# OneButton.net
KiCad netlist of a schematic drawn in EAGLE
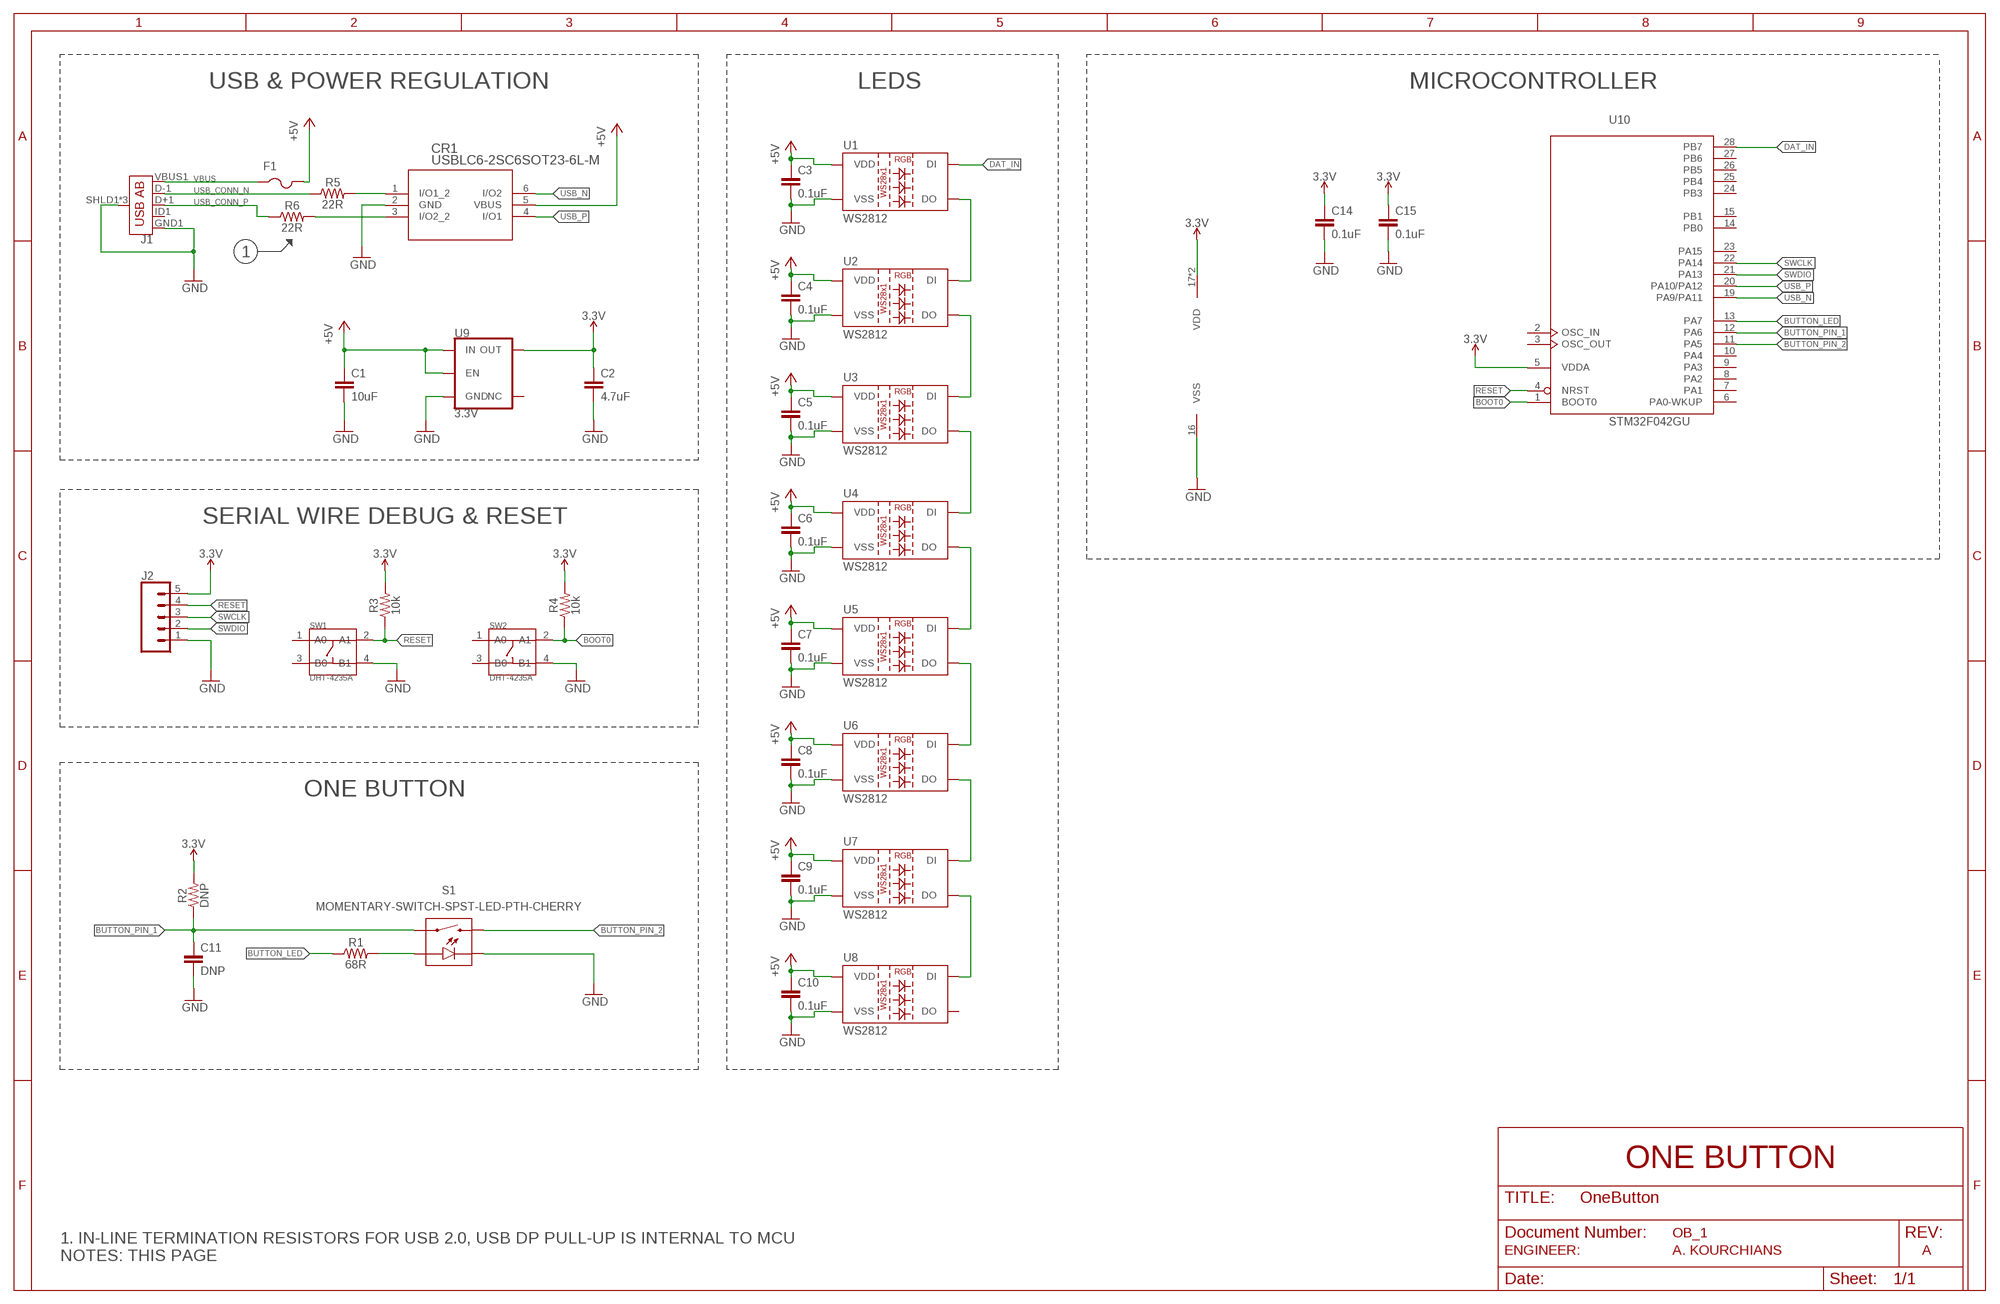
[diagram p0: schematic, sheet 1]

(export (version "E")
  (design (tool "Eeschema 10.0.6"))
  (components
    (comp (ref "C1")
      (value "10uF")
      (footprint "eagle-import:CAP-1206")
      (libsource (lib "eagle-import") (part "10UFCAP-1206"))
    )
    (comp (ref "C2")
      (value "4.7uF")
      (footprint "eagle-import:CAP-1206")
      (libsource (lib "eagle-import") (part "4.7UFCAP-1206"))
    )
    (comp (ref "C3")
      (value "0.1uF")
      (footprint "eagle-import:CAP-0603")
      (libsource (lib "eagle-import") (part "0.1UFCAP-0603"))
    )
    (comp (ref "C4")
      (value "0.1uF")
      (footprint "eagle-import:CAP-0603")
      (libsource (lib "eagle-import") (part "0.1UFCAP-0603"))
    )
    (comp (ref "C5")
      (value "0.1uF")
      (footprint "eagle-import:CAP-0603")
      (libsource (lib "eagle-import") (part "0.1UFCAP-0603"))
    )
    (comp (ref "C6")
      (value "0.1uF")
      (footprint "eagle-import:CAP-0603")
      (libsource (lib "eagle-import") (part "0.1UFCAP-0603"))
    )
    (comp (ref "C7")
      (value "0.1uF")
      (footprint "eagle-import:CAP-0603")
      (libsource (lib "eagle-import") (part "0.1UFCAP-0603"))
    )
    (comp (ref "C8")
      (value "0.1uF")
      (footprint "eagle-import:CAP-0603")
      (libsource (lib "eagle-import") (part "0.1UFCAP-0603"))
    )
    (comp (ref "C9")
      (value "0.1uF")
      (footprint "eagle-import:CAP-0603")
      (libsource (lib "eagle-import") (part "0.1UFCAP-0603"))
    )
    (comp (ref "C10")
      (value "0.1uF")
      (footprint "eagle-import:CAP-0603")
      (libsource (lib "eagle-import") (part "0.1UFCAP-0603"))
    )
    (comp (ref "C11")
      (value "DNP")
      (footprint "eagle-import:CAP-0603")
      (libsource (lib "eagle-import") (part "CAPACITORCAP-0603"))
    )
    (comp (ref "C14")
      (value "0.1uF")
      (footprint "eagle-import:CAP-0603")
      (libsource (lib "eagle-import") (part "0.1UFCAP-0603"))
    )
    (comp (ref "C15")
      (value "0.1uF")
      (footprint "eagle-import:CAP-0603")
      (libsource (lib "eagle-import") (part "0.1UFCAP-0603"))
    )
    (comp (ref "CR1")
      (value "USBLC6-2SC6SOT23-6L-M")
      (footprint "eagle-import:SOT23-6L-M")
      (fields (field (name "MANUFACTURER_PART_NUMBER") "USBLC62SC6"))
      (libsource (lib "eagle-import") (part "USBLC6-2SC6SOT23-6L-M"))
    )
    (comp (ref "F1")
      (value "PTCFUSE-1206")
      (footprint "eagle-import:R1206")
      (libsource (lib "eagle-import") (part "PTCFUSE-1206"))
    )
    (comp (ref "J1")
      (value "USB_AB_SMT")
      (footprint "eagle-import:USB-AB-MICRO-SMD")
      (libsource (lib "eagle-import") (part "USB_AB_SMT"))
    )
    (comp (ref "J2")
      (value "CONN_05")
      (footprint "eagle-import:1X05")
      (libsource (lib "eagle-import") (part "CONN_05"))
    )
    (comp (ref "R1")
      (value "68R")
      (footprint "eagle-import:RESC0603_N")
      (libsource (lib "eagle-import") (part "RESISTORRES-0603"))
    )
    (comp (ref "R2")
      (value "DNP")
      (footprint "eagle-import:RESC0603_N")
      (libsource (lib "eagle-import") (part "RESISTORRES-0603"))
    )
    (comp (ref "R3")
      (value "10k")
      (footprint "eagle-import:RESC0603_N")
      (libsource (lib "eagle-import") (part "RESISTORRES-0603"))
    )
    (comp (ref "R4")
      (value "10k")
      (footprint "eagle-import:RESC0603_N")
      (libsource (lib "eagle-import") (part "RESISTORRES-0603"))
    )
    (comp (ref "R5")
      (value "22R")
      (footprint "eagle-import:RESC0603_N")
      (libsource (lib "eagle-import") (part "RESISTORRES-0603"))
    )
    (comp (ref "R6")
      (value "22R")
      (footprint "eagle-import:RESC0603_N")
      (libsource (lib "eagle-import") (part "RESISTORRES-0603"))
    )
    (comp (ref "S1")
      (value "MOMENTARY-SWITCH-SPST-LED-PTH-CHERRY")
      (footprint "eagle-import:CHERRY-MX-LED")
      (fields (field (name "SPICEPREFIX") "S"))
      (libsource (lib "eagle-import") (part "MOMENTARY-SWITCH-SPST-LED-PTH-CHERRY"))
    )
    (comp (ref "SW1")
      (value "DHT-4235A")
      (footprint "eagle-import:SW4-SMD-4.2X3.2X2.5MM")
      (libsource (lib "eagle-import") (part "SMD-BUTTON-TOP-DHT-4235A(4P-4.2X3.2MM)"))
    )
    (comp (ref "SW2")
      (value "DHT-4235A")
      (footprint "eagle-import:SW4-SMD-4.2X3.2X2.5MM")
      (libsource (lib "eagle-import") (part "SMD-BUTTON-TOP-DHT-4235A(4P-4.2X3.2MM)"))
    )
    (comp (ref "U1")
      (value "WS2812")
      (footprint "eagle-import:LED-TRICOLOR-5050-IC")
      (libsource (lib "eagle-import") (part "WS2812{dblquote}"))
    )
    (comp (ref "U2")
      (value "WS2812")
      (footprint "eagle-import:LED-TRICOLOR-5050-IC")
      (libsource (lib "eagle-import") (part "WS2812{dblquote}"))
    )
    (comp (ref "U3")
      (value "WS2812")
      (footprint "eagle-import:LED-TRICOLOR-5050-IC")
      (libsource (lib "eagle-import") (part "WS2812{dblquote}"))
    )
    (comp (ref "U4")
      (value "WS2812")
      (footprint "eagle-import:LED-TRICOLOR-5050-IC")
      (libsource (lib "eagle-import") (part "WS2812{dblquote}"))
    )
    (comp (ref "U5")
      (value "WS2812")
      (footprint "eagle-import:LED-TRICOLOR-5050-IC")
      (libsource (lib "eagle-import") (part "WS2812{dblquote}"))
    )
    (comp (ref "U6")
      (value "WS2812")
      (footprint "eagle-import:LED-TRICOLOR-5050-IC")
      (libsource (lib "eagle-import") (part "WS2812{dblquote}"))
    )
    (comp (ref "U7")
      (value "WS2812")
      (footprint "eagle-import:LED-TRICOLOR-5050-IC")
      (libsource (lib "eagle-import") (part "WS2812{dblquote}"))
    )
    (comp (ref "U8")
      (value "WS2812")
      (footprint "eagle-import:LED-TRICOLOR-5050-IC")
      (libsource (lib "eagle-import") (part "WS2812{dblquote}"))
    )
    (comp (ref "U9")
      (value "3.3V")
      (footprint "eagle-import:SOT23-5")
      (libsource (lib "eagle-import") (part "V_REG_AP2112K-3.3V"))
    )
    (comp (ref "U10")
      (value "STM32F042GU")
      (footprint "eagle-import:UFQFPN28")
      (libsource (lib "eagle-import") (part "STM32F042GU"))
    )
  )
  (nets
    (net (code "1") (name "+5V") (class "Default")
      (node (ref "C1") (pin "1") (pinfunction "1_1") (pintype "passive"))
      (node (ref "C10") (pin "1") (pinfunction "1_1") (pintype "passive"))
      (node (ref "C3") (pin "1") (pinfunction "1_1") (pintype "passive"))
      (node (ref "C4") (pin "1") (pinfunction "1_1") (pintype "passive"))
      (node (ref "C5") (pin "1") (pinfunction "1_1") (pintype "passive"))
      (node (ref "C6") (pin "1") (pinfunction "1_1") (pintype "passive"))
      (node (ref "C7") (pin "1") (pinfunction "1_1") (pintype "passive"))
      (node (ref "C8") (pin "1") (pinfunction "1_1") (pintype "passive"))
      (node (ref "C9") (pin "1") (pinfunction "1_1") (pintype "passive"))
      (node (ref "CR1") (pin "5") (pinfunction "VBUS_5") (pintype "power_in"))
      (node (ref "F1") (pin "2") (pinfunction "2_2") (pintype "passive"))
      (node (ref "U1") (pin "3") (pinfunction "VDD_3") (pintype "bidirectional"))
      (node (ref "U1") (pin "5") (pinfunction "VDD_5") (pintype "bidirectional"))
      (node (ref "U2") (pin "3") (pinfunction "VDD_3") (pintype "bidirectional"))
      (node (ref "U2") (pin "5") (pinfunction "VDD_5") (pintype "bidirectional"))
      (node (ref "U3") (pin "3") (pinfunction "VDD_3") (pintype "bidirectional"))
      (node (ref "U3") (pin "5") (pinfunction "VDD_5") (pintype "bidirectional"))
      (node (ref "U4") (pin "3") (pinfunction "VDD_3") (pintype "bidirectional"))
      (node (ref "U4") (pin "5") (pinfunction "VDD_5") (pintype "bidirectional"))
      (node (ref "U5") (pin "3") (pinfunction "VDD_3") (pintype "bidirectional"))
      (node (ref "U5") (pin "5") (pinfunction "VDD_5") (pintype "bidirectional"))
      (node (ref "U6") (pin "3") (pinfunction "VDD_3") (pintype "bidirectional"))
      (node (ref "U6") (pin "5") (pinfunction "VDD_5") (pintype "bidirectional"))
      (node (ref "U7") (pin "3") (pinfunction "VDD_3") (pintype "bidirectional"))
      (node (ref "U7") (pin "5") (pinfunction "VDD_5") (pintype "bidirectional"))
      (node (ref "U8") (pin "3") (pinfunction "VDD_3") (pintype "bidirectional"))
      (node (ref "U8") (pin "5") (pinfunction "VDD_5") (pintype "bidirectional"))
      (node (ref "U9") (pin "1") (pinfunction "IN_1") (pintype "input"))
      (node (ref "U9") (pin "3") (pinfunction "EN_3") (pintype "input"))
    )
    (net (code "2") (name "/USB_CONN_N") (class "Default")
      (node (ref "J1") (pin "D-1") (pinfunction "D-_D-1") (pintype "bidirectional"))
      (node (ref "R5") (pin "1") (pinfunction "1_1") (pintype "passive"))
    )
    (net (code "3") (name "/USB_CONN_P") (class "Default")
      (node (ref "J1") (pin "D+1") (pinfunction "D+_D+1") (pintype "bidirectional"))
      (node (ref "R6") (pin "1") (pinfunction "1_1") (pintype "passive"))
    )
    (net (code "4") (name "/VBUS") (class "Default")
      (node (ref "F1") (pin "1") (pinfunction "1_1") (pintype "passive"))
      (node (ref "J1") (pin "VBUS1") (pinfunction "VBUS_VBUS1") (pintype "power_in"))
    )
    (net (code "5") (name "3.3V") (class "Default")
      (node (ref "C14") (pin "1") (pinfunction "1_1") (pintype "passive"))
      (node (ref "C15") (pin "1") (pinfunction "1_1") (pintype "passive"))
      (node (ref "C2") (pin "1") (pinfunction "1_1") (pintype "passive"))
      (node (ref "J2") (pin "5") (pinfunction "5_5") (pintype "passive"))
      (node (ref "R2") (pin "2") (pinfunction "2_2") (pintype "passive"))
      (node (ref "R3") (pin "2") (pinfunction "2_2") (pintype "passive"))
      (node (ref "R4") (pin "2") (pinfunction "2_2") (pintype "passive"))
      (node (ref "U10") (pin "17") (pinfunction "VDD_17") (pintype "power_in"))
      (node (ref "U10") (pin "18") (pinfunction "VDD_18") (pintype "power_in"))
      (node (ref "U10") (pin "5") (pinfunction "VDDA_5") (pintype "power_in"))
      (node (ref "U9") (pin "5") (pinfunction "OUT_5") (pintype "passive"))
    )
    (net (code "6") (name "BOOT0") (class "Default")
      (node (ref "R4") (pin "1") (pinfunction "1_1") (pintype "passive"))
      (node (ref "SW2") (pin "2") (pinfunction "A1_2") (pintype "bidirectional"))
      (node (ref "U10") (pin "1") (pinfunction "BOOT0_1") (pintype "input"))
    )
    (net (code "7") (name "BUTTON_LED") (class "Default")
      (node (ref "R1") (pin "1") (pinfunction "1_1") (pintype "passive"))
      (node (ref "U10") (pin "13") (pinfunction "PA7_13") (pintype "bidirectional"))
    )
    (net (code "8") (name "BUTTON_PIN_1") (class "Default")
      (node (ref "C11") (pin "1") (pinfunction "1_1") (pintype "passive"))
      (node (ref "R2") (pin "1") (pinfunction "1_1") (pintype "passive"))
      (node (ref "S1") (pin "S1") (pinfunction "1_S1") (pintype "passive"))
      (node (ref "U10") (pin "12") (pinfunction "PA6_12") (pintype "bidirectional"))
    )
    (net (code "9") (name "BUTTON_PIN_2") (class "Default")
      (node (ref "S1") (pin "S2") (pinfunction "2_S2") (pintype "passive"))
      (node (ref "U10") (pin "11") (pinfunction "PA5_11") (pintype "bidirectional"))
    )
    (net (code "10") (name "DAT_IN") (class "Default")
      (node (ref "U1") (pin "2") (pinfunction "DI_2") (pintype "bidirectional"))
      (node (ref "U10") (pin "28") (pinfunction "PB7_28") (pintype "bidirectional"))
    )
    (net (code "11") (name "GND") (class "Default")
      (node (ref "C1") (pin "2") (pinfunction "2_2") (pintype "passive"))
      (node (ref "C10") (pin "2") (pinfunction "2_2") (pintype "passive"))
      (node (ref "C11") (pin "2") (pinfunction "2_2") (pintype "passive"))
      (node (ref "C14") (pin "2") (pinfunction "2_2") (pintype "passive"))
      (node (ref "C15") (pin "2") (pinfunction "2_2") (pintype "passive"))
      (node (ref "C2") (pin "2") (pinfunction "2_2") (pintype "passive"))
      (node (ref "C3") (pin "2") (pinfunction "2_2") (pintype "passive"))
      (node (ref "C4") (pin "2") (pinfunction "2_2") (pintype "passive"))
      (node (ref "C5") (pin "2") (pinfunction "2_2") (pintype "passive"))
      (node (ref "C6") (pin "2") (pinfunction "2_2") (pintype "passive"))
      (node (ref "C7") (pin "2") (pinfunction "2_2") (pintype "passive"))
      (node (ref "C8") (pin "2") (pinfunction "2_2") (pintype "passive"))
      (node (ref "C9") (pin "2") (pinfunction "2_2") (pintype "passive"))
      (node (ref "CR1") (pin "2") (pinfunction "GND_2") (pintype "power_in"))
      (node (ref "J1") (pin "GND1") (pinfunction "GND_GND1") (pintype "power_in"))
      (node (ref "J1") (pin "SHLD1") (pinfunction "SHIELD_SHLD1") (pintype "bidirectional"))
      (node (ref "J1") (pin "SHLD2") (pinfunction "SHIELD_SHLD2") (pintype "bidirectional"))
      (node (ref "J1") (pin "SHLD3") (pinfunction "SHIELD_SHLD3") (pintype "bidirectional"))
      (node (ref "J2") (pin "1") (pinfunction "1_1") (pintype "passive"))
      (node (ref "S1") (pin "K") (pinfunction "C_K") (pintype "passive"))
      (node (ref "S1") (pin "K1") (pinfunction "C_K1") (pintype "passive"))
      (node (ref "SW1") (pin "4") (pinfunction "B1_4") (pintype "bidirectional"))
      (node (ref "SW2") (pin "4") (pinfunction "B1_4") (pintype "bidirectional"))
      (node (ref "U1") (pin "6") (pinfunction "VSS_6") (pintype "bidirectional"))
      (node (ref "U10") (pin "16") (pinfunction "VSS_16") (pintype "power_in"))
      (node (ref "U2") (pin "6") (pinfunction "VSS_6") (pintype "bidirectional"))
      (node (ref "U3") (pin "6") (pinfunction "VSS_6") (pintype "bidirectional"))
      (node (ref "U4") (pin "6") (pinfunction "VSS_6") (pintype "bidirectional"))
      (node (ref "U5") (pin "6") (pinfunction "VSS_6") (pintype "bidirectional"))
      (node (ref "U6") (pin "6") (pinfunction "VSS_6") (pintype "bidirectional"))
      (node (ref "U7") (pin "6") (pinfunction "VSS_6") (pintype "bidirectional"))
      (node (ref "U8") (pin "6") (pinfunction "VSS_6") (pintype "bidirectional"))
      (node (ref "U9") (pin "2") (pinfunction "GND_2") (pintype "input"))
    )
    (net (code "12") (name "Net-(CR1-I{slash}O1_2)") (class "Default")
      (node (ref "CR1") (pin "1") (pinfunction "I/O1_2_1") (pintype "bidirectional"))
      (node (ref "R5") (pin "2") (pinfunction "2_2") (pintype "passive"))
    )
    (net (code "13") (name "Net-(CR1-I{slash}O2_2)") (class "Default")
      (node (ref "CR1") (pin "3") (pinfunction "I/O2_2_3") (pintype "bidirectional"))
      (node (ref "R6") (pin "2") (pinfunction "2_2") (pintype "passive"))
    )
    (net (code "14") (name "Net-(R1-Pad2)") (class "Default")
      (node (ref "R1") (pin "2") (pinfunction "2_2") (pintype "passive"))
      (node (ref "S1") (pin "A") (pinfunction "A_A") (pintype "passive"))
      (node (ref "S1") (pin "A1") (pinfunction "A_A1") (pintype "passive"))
    )
    (net (code "15") (name "Net-(U1-DO)") (class "Default")
      (node (ref "U1") (pin "1") (pinfunction "DO_1") (pintype "bidirectional"))
      (node (ref "U2") (pin "2") (pinfunction "DI_2") (pintype "bidirectional"))
    )
    (net (code "16") (name "Net-(U2-DO)") (class "Default")
      (node (ref "U2") (pin "1") (pinfunction "DO_1") (pintype "bidirectional"))
      (node (ref "U3") (pin "2") (pinfunction "DI_2") (pintype "bidirectional"))
    )
    (net (code "17") (name "Net-(U3-DO)") (class "Default")
      (node (ref "U3") (pin "1") (pinfunction "DO_1") (pintype "bidirectional"))
      (node (ref "U4") (pin "2") (pinfunction "DI_2") (pintype "bidirectional"))
    )
    (net (code "18") (name "Net-(U4-DO)") (class "Default")
      (node (ref "U4") (pin "1") (pinfunction "DO_1") (pintype "bidirectional"))
      (node (ref "U5") (pin "2") (pinfunction "DI_2") (pintype "bidirectional"))
    )
    (net (code "19") (name "Net-(U5-DO)") (class "Default")
      (node (ref "U5") (pin "1") (pinfunction "DO_1") (pintype "bidirectional"))
      (node (ref "U6") (pin "2") (pinfunction "DI_2") (pintype "bidirectional"))
    )
    (net (code "20") (name "Net-(U6-DO)") (class "Default")
      (node (ref "U6") (pin "1") (pinfunction "DO_1") (pintype "bidirectional"))
      (node (ref "U7") (pin "2") (pinfunction "DI_2") (pintype "bidirectional"))
    )
    (net (code "21") (name "Net-(U7-DO)") (class "Default")
      (node (ref "U7") (pin "1") (pinfunction "DO_1") (pintype "bidirectional"))
      (node (ref "U8") (pin "2") (pinfunction "DI_2") (pintype "bidirectional"))
    )
    (net (code "22") (name "RESET") (class "Default")
      (node (ref "J2") (pin "4") (pinfunction "4_4") (pintype "passive"))
      (node (ref "R3") (pin "1") (pinfunction "1_1") (pintype "passive"))
      (node (ref "SW1") (pin "2") (pinfunction "A1_2") (pintype "bidirectional"))
      (node (ref "U10") (pin "4") (pinfunction "NRST_4") (pintype "bidirectional"))
    )
    (net (code "23") (name "SWCLK") (class "Default")
      (node (ref "J2") (pin "3") (pinfunction "3_3") (pintype "passive"))
      (node (ref "U10") (pin "22") (pinfunction "PA14_22") (pintype "bidirectional"))
    )
    (net (code "24") (name "SWDIO") (class "Default")
      (node (ref "J2") (pin "2") (pinfunction "2_2") (pintype "passive"))
      (node (ref "U10") (pin "21") (pinfunction "PA13_21") (pintype "bidirectional"))
    )
    (net (code "25") (name "USB_N") (class "Default")
      (node (ref "CR1") (pin "6") (pinfunction "I/O2_6") (pintype "bidirectional"))
      (node (ref "U10") (pin "19") (pinfunction "PA9/PA11_19") (pintype "bidirectional"))
    )
    (net (code "26") (name "USB_P") (class "Default")
      (node (ref "CR1") (pin "4") (pinfunction "I/O1_4") (pintype "bidirectional"))
      (node (ref "U10") (pin "20") (pinfunction "PA10/PA12_20") (pintype "bidirectional"))
    )
    (net (code "27") (name "unconnected-(J1-USBID-PadID1)") (class "Default")
      (node (ref "J1") (pin "ID1") (pinfunction "USBID_ID1") (pintype "bidirectional"))
    )
    (net (code "28") (name "unconnected-(SW1-A0-Pad1)") (class "Default")
      (node (ref "SW1") (pin "1") (pinfunction "A0_1") (pintype "bidirectional"))
    )
    (net (code "29") (name "unconnected-(SW1-B0-Pad3)") (class "Default")
      (node (ref "SW1") (pin "3") (pinfunction "B0_3") (pintype "bidirectional"))
    )
    (net (code "30") (name "unconnected-(SW2-A0-Pad1)") (class "Default")
      (node (ref "SW2") (pin "1") (pinfunction "A0_1") (pintype "bidirectional"))
    )
    (net (code "31") (name "unconnected-(SW2-B0-Pad3)") (class "Default")
      (node (ref "SW2") (pin "3") (pinfunction "B0_3") (pintype "bidirectional"))
    )
    (net (code "32") (name "unconnected-(U8-DO-Pad1)") (class "Default")
      (node (ref "U8") (pin "1") (pinfunction "DO_1") (pintype "bidirectional"))
    )
    (net (code "33") (name "unconnected-(U9-NC-Pad4)") (class "Default")
      (node (ref "U9") (pin "4") (pinfunction "NC_4") (pintype "no_connect"))
    )
    (net (code "34") (name "unconnected-(U10A-OSC_IN-Pad2)") (class "Default")
      (node (ref "U10") (pin "2") (pinfunction "OSC_IN_2") (pintype "bidirectional"))
    )
    (net (code "35") (name "unconnected-(U10A-OSC_OUT-Pad3)") (class "Default")
      (node (ref "U10") (pin "3") (pinfunction "OSC_OUT_3") (pintype "bidirectional"))
    )
    (net (code "36") (name "unconnected-(U10A-PA0-WKUP-Pad6)") (class "Default")
      (node (ref "U10") (pin "6") (pinfunction "PA0-WKUP_6") (pintype "bidirectional"))
    )
    (net (code "37") (name "unconnected-(U10A-PA1-Pad7)") (class "Default")
      (node (ref "U10") (pin "7") (pinfunction "PA1_7") (pintype "bidirectional"))
    )
    (net (code "38") (name "unconnected-(U10A-PA2-Pad8)") (class "Default")
      (node (ref "U10") (pin "8") (pinfunction "PA2_8") (pintype "bidirectional"))
    )
    (net (code "39") (name "unconnected-(U10A-PA3-Pad9)") (class "Default")
      (node (ref "U10") (pin "9") (pinfunction "PA3_9") (pintype "bidirectional"))
    )
    (net (code "40") (name "unconnected-(U10A-PA4-Pad10)") (class "Default")
      (node (ref "U10") (pin "10") (pinfunction "PA4_10") (pintype "bidirectional"))
    )
    (net (code "41") (name "unconnected-(U10A-PA15-Pad23)") (class "Default")
      (node (ref "U10") (pin "23") (pinfunction "PA15_23") (pintype "bidirectional"))
    )
    (net (code "42") (name "unconnected-(U10A-PB0-Pad14)") (class "Default")
      (node (ref "U10") (pin "14") (pinfunction "PB0_14") (pintype "bidirectional"))
    )
    (net (code "43") (name "unconnected-(U10A-PB1-Pad15)") (class "Default")
      (node (ref "U10") (pin "15") (pinfunction "PB1_15") (pintype "bidirectional"))
    )
    (net (code "44") (name "unconnected-(U10A-PB3-Pad24)") (class "Default")
      (node (ref "U10") (pin "24") (pinfunction "PB3_24") (pintype "bidirectional"))
    )
    (net (code "45") (name "unconnected-(U10A-PB4-Pad25)") (class "Default")
      (node (ref "U10") (pin "25") (pinfunction "PB4_25") (pintype "bidirectional"))
    )
    (net (code "46") (name "unconnected-(U10A-PB5-Pad26)") (class "Default")
      (node (ref "U10") (pin "26") (pinfunction "PB5_26") (pintype "bidirectional"))
    )
    (net (code "47") (name "unconnected-(U10A-PB6-Pad27)") (class "Default")
      (node (ref "U10") (pin "27") (pinfunction "PB6_27") (pintype "bidirectional"))
    )
  )
)
